# usomiq.net
KiCad netlist of a schematic drawn in Altium Designer
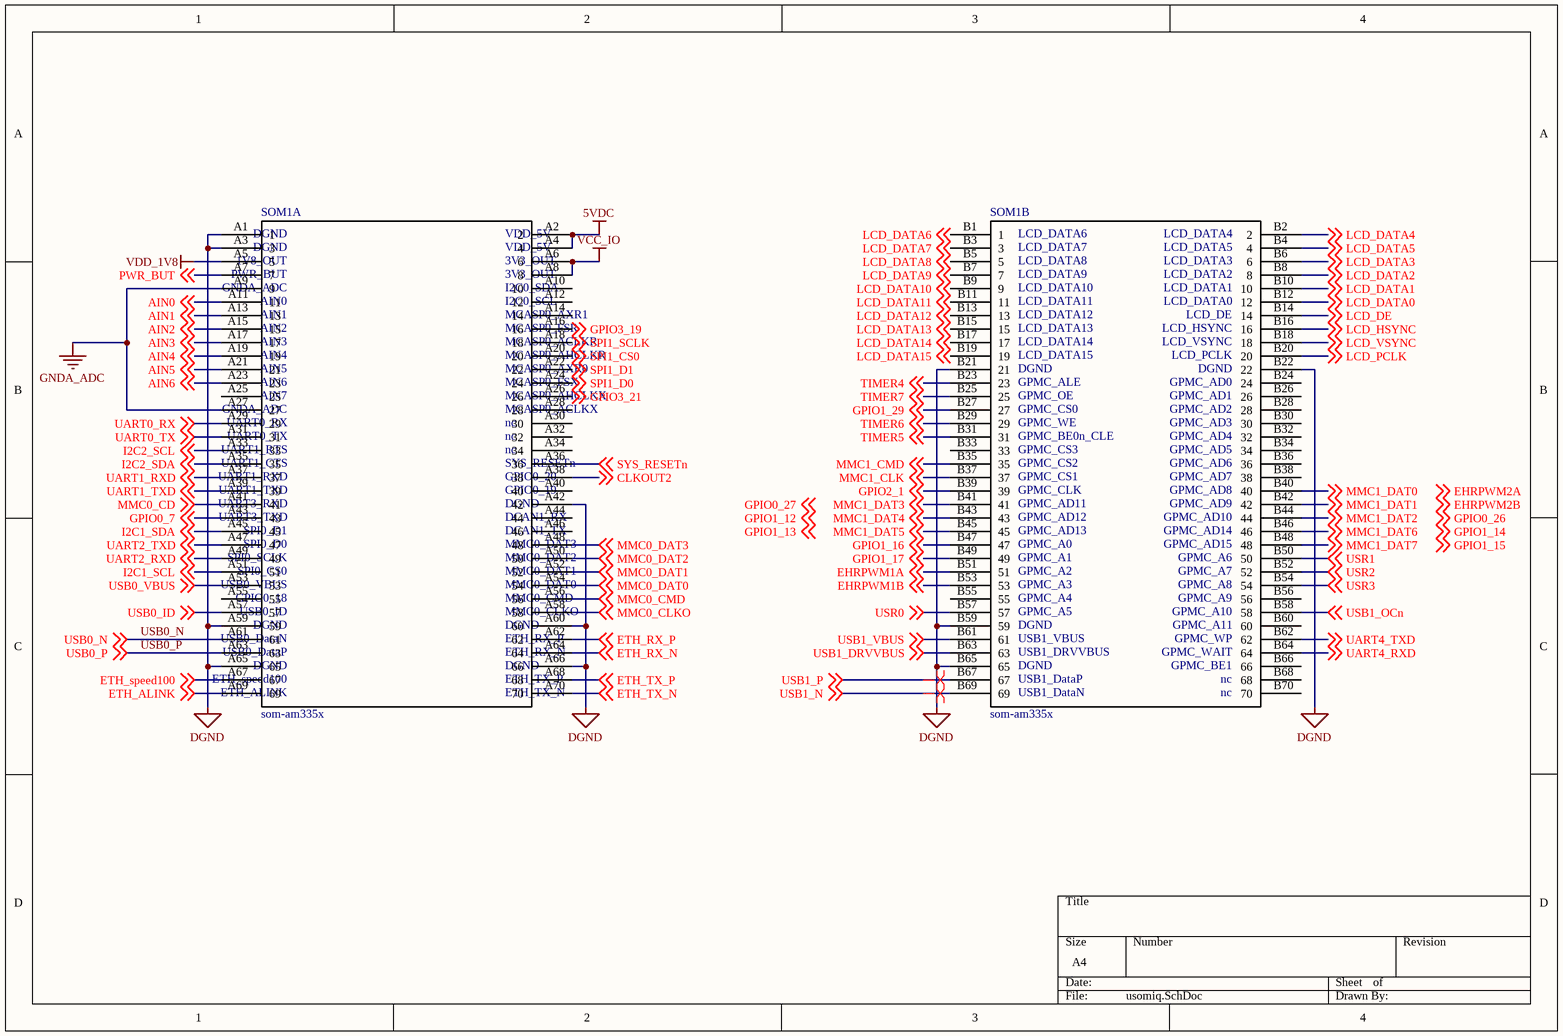
[diagram p0: usomiq.SchDoc]

(export (version "E")
  (design (tool "Eeschema 10.0.6"))
  (components
    (comp (ref "SOM1")
      (value "som-am335x")
      (footprint "am3359_module-sockets")
      (libsource (lib "usomiq-base") (part "som-am335x"))
    )
  )
  (nets
    (net (code "1") (name "5VDC") (class "Default")
      (node (ref "SOM1") (pin "A2") (pinfunction "2_A2") (pintype "passive"))
      (node (ref "SOM1") (pin "A4") (pinfunction "4_A4") (pintype "passive"))
    )
    (net (code "2") (name "AIN0") (class "Default")
      (node (ref "SOM1") (pin "A11") (pinfunction "11_A11") (pintype "passive"))
    )
    (net (code "3") (name "AIN1") (class "Default")
      (node (ref "SOM1") (pin "A13") (pinfunction "13_A13") (pintype "passive"))
    )
    (net (code "4") (name "AIN2") (class "Default")
      (node (ref "SOM1") (pin "A15") (pinfunction "15_A15") (pintype "passive"))
    )
    (net (code "5") (name "AIN3") (class "Default")
      (node (ref "SOM1") (pin "A17") (pinfunction "17_A17") (pintype "passive"))
    )
    (net (code "6") (name "AIN4") (class "Default")
      (node (ref "SOM1") (pin "A19") (pinfunction "19_A19") (pintype "passive"))
    )
    (net (code "7") (name "AIN5") (class "Default")
      (node (ref "SOM1") (pin "A21") (pinfunction "21_A21") (pintype "passive"))
    )
    (net (code "8") (name "AIN6") (class "Default")
      (node (ref "SOM1") (pin "A23") (pinfunction "23_A23") (pintype "passive"))
    )
    (net (code "9") (name "CLKOUT2") (class "Default")
      (node (ref "SOM1") (pin "A38") (pinfunction "38_A38") (pintype "passive"))
    )
    (net (code "10") (name "DGND") (class "Default")
      (node (ref "SOM1") (pin "A1") (pinfunction "1_A1") (pintype "passive"))
      (node (ref "SOM1") (pin "A3") (pinfunction "3_A3") (pintype "passive"))
      (node (ref "SOM1") (pin "A42") (pinfunction "42_A42") (pintype "passive"))
      (node (ref "SOM1") (pin "A59") (pinfunction "59_A59") (pintype "passive"))
      (node (ref "SOM1") (pin "A60") (pinfunction "60_A60") (pintype "passive"))
      (node (ref "SOM1") (pin "A65") (pinfunction "65_A65") (pintype "passive"))
      (node (ref "SOM1") (pin "A66") (pinfunction "66_A66") (pintype "passive"))
      (node (ref "SOM1") (pin "B21") (pinfunction "21_B21") (pintype "passive"))
      (node (ref "SOM1") (pin "B22") (pinfunction "22_B22") (pintype "passive"))
      (node (ref "SOM1") (pin "B59") (pinfunction "59_B59") (pintype "passive"))
      (node (ref "SOM1") (pin "B65") (pinfunction "65_B65") (pintype "passive"))
    )
    (net (code "11") (name "EHRPWM1A") (class "Default")
      (node (ref "SOM1") (pin "B51") (pinfunction "51_B51") (pintype "passive"))
    )
    (net (code "12") (name "EHRPWM1B") (class "Default")
      (node (ref "SOM1") (pin "B53") (pinfunction "53_B53") (pintype "passive"))
    )
    (net (code "15") (name "ETH_ALINK") (class "Default")
      (node (ref "SOM1") (pin "A69") (pinfunction "69_A69") (pintype "passive"))
    )
    (net (code "16") (name "ETH_RX_N") (class "Default")
      (node (ref "SOM1") (pin "A64") (pinfunction "64_A64") (pintype "passive"))
    )
    (net (code "17") (name "ETH_RX_P") (class "Default")
      (node (ref "SOM1") (pin "A62") (pinfunction "62_A62") (pintype "passive"))
    )
    (net (code "18") (name "ETH_TX_N") (class "Default")
      (node (ref "SOM1") (pin "A70") (pinfunction "70_A70") (pintype "passive"))
    )
    (net (code "19") (name "ETH_TX_P") (class "Default")
      (node (ref "SOM1") (pin "A68") (pinfunction "68_A68") (pintype "passive"))
    )
    (net (code "20") (name "ETH_speed100") (class "Default")
      (node (ref "SOM1") (pin "A67") (pinfunction "67_A67") (pintype "passive"))
    )
    (net (code "21") (name "GNDA_ADC") (class "Default")
      (node (ref "SOM1") (pin "A27") (pinfunction "27_A27") (pintype "passive"))
      (node (ref "SOM1") (pin "A9") (pinfunction "9_A9") (pintype "passive"))
    )
    (net (code "22") (name "GPIO0_7") (class "Default")
      (node (ref "SOM1") (pin "A43") (pinfunction "43_A43") (pintype "passive"))
    )
    (net (code "29") (name "GPIO1_16") (class "Default")
      (node (ref "SOM1") (pin "B47") (pinfunction "47_B47") (pintype "passive"))
    )
    (net (code "30") (name "GPIO1_17") (class "Default")
      (node (ref "SOM1") (pin "B49") (pinfunction "49_B49") (pintype "passive"))
    )
    (net (code "31") (name "GPIO1_29") (class "Default")
      (node (ref "SOM1") (pin "B27") (pinfunction "27_B27") (pintype "passive"))
    )
    (net (code "32") (name "GPIO2_1") (class "Default")
      (node (ref "SOM1") (pin "B39") (pinfunction "39_B39") (pintype "passive"))
    )
    (net (code "33") (name "GPIO3_19") (class "Default")
      (node (ref "SOM1") (pin "A16") (pinfunction "16_A16") (pintype "passive"))
    )
    (net (code "34") (name "GPIO3_21") (class "Default")
      (node (ref "SOM1") (pin "A26") (pinfunction "26_A26") (pintype "passive"))
    )
    (net (code "35") (name "I2C1_SCL") (class "Default")
      (node (ref "SOM1") (pin "A51") (pinfunction "51_A51") (pintype "passive"))
    )
    (net (code "36") (name "I2C1_SDA") (class "Default")
      (node (ref "SOM1") (pin "A45") (pinfunction "45_A45") (pintype "passive"))
    )
    (net (code "37") (name "I2C2_SCL") (class "Default")
      (node (ref "SOM1") (pin "A33") (pinfunction "33_A33") (pintype "passive"))
    )
    (net (code "38") (name "I2C2_SDA") (class "Default")
      (node (ref "SOM1") (pin "A35") (pinfunction "35_A35") (pintype "passive"))
    )
    (net (code "39") (name "LCD_DATA0") (class "Default")
      (node (ref "SOM1") (pin "B12") (pinfunction "12_B12") (pintype "passive"))
    )
    (net (code "40") (name "LCD_DATA1") (class "Default")
      (node (ref "SOM1") (pin "B10") (pinfunction "10_B10") (pintype "passive"))
    )
    (net (code "41") (name "LCD_DATA2") (class "Default")
      (node (ref "SOM1") (pin "B8") (pinfunction "8_B8") (pintype "passive"))
    )
    (net (code "42") (name "LCD_DATA3") (class "Default")
      (node (ref "SOM1") (pin "B6") (pinfunction "6_B6") (pintype "passive"))
    )
    (net (code "43") (name "LCD_DATA4") (class "Default")
      (node (ref "SOM1") (pin "B2") (pinfunction "2_B2") (pintype "passive"))
    )
    (net (code "44") (name "LCD_DATA5") (class "Default")
      (node (ref "SOM1") (pin "B4") (pinfunction "4_B4") (pintype "passive"))
    )
    (net (code "45") (name "LCD_DATA6") (class "Default")
      (node (ref "SOM1") (pin "B1") (pinfunction "1_B1") (pintype "passive"))
    )
    (net (code "46") (name "LCD_DATA7") (class "Default")
      (node (ref "SOM1") (pin "B3") (pinfunction "3_B3") (pintype "passive"))
    )
    (net (code "47") (name "LCD_DATA8") (class "Default")
      (node (ref "SOM1") (pin "B5") (pinfunction "5_B5") (pintype "passive"))
    )
    (net (code "48") (name "LCD_DATA9") (class "Default")
      (node (ref "SOM1") (pin "B7") (pinfunction "7_B7") (pintype "passive"))
    )
    (net (code "49") (name "LCD_DATA10") (class "Default")
      (node (ref "SOM1") (pin "B9") (pinfunction "9_B9") (pintype "passive"))
    )
    (net (code "50") (name "LCD_DATA11") (class "Default")
      (node (ref "SOM1") (pin "B11") (pinfunction "11_B11") (pintype "passive"))
    )
    (net (code "51") (name "LCD_DATA12") (class "Default")
      (node (ref "SOM1") (pin "B13") (pinfunction "13_B13") (pintype "passive"))
    )
    (net (code "52") (name "LCD_DATA13") (class "Default")
      (node (ref "SOM1") (pin "B15") (pinfunction "15_B15") (pintype "passive"))
    )
    (net (code "53") (name "LCD_DATA14") (class "Default")
      (node (ref "SOM1") (pin "B17") (pinfunction "17_B17") (pintype "passive"))
    )
    (net (code "54") (name "LCD_DATA15") (class "Default")
      (node (ref "SOM1") (pin "B19") (pinfunction "19_B19") (pintype "passive"))
    )
    (net (code "55") (name "LCD_DE") (class "Default")
      (node (ref "SOM1") (pin "B14") (pinfunction "14_B14") (pintype "passive"))
    )
    (net (code "56") (name "LCD_HSYNC") (class "Default")
      (node (ref "SOM1") (pin "B16") (pinfunction "16_B16") (pintype "passive"))
    )
    (net (code "57") (name "LCD_PCLK") (class "Default")
      (node (ref "SOM1") (pin "B20") (pinfunction "20_B20") (pintype "passive"))
    )
    (net (code "58") (name "LCD_VSYNC") (class "Default")
      (node (ref "SOM1") (pin "B18") (pinfunction "18_B18") (pintype "passive"))
    )
    (net (code "59") (name "MMC0_CD") (class "Default")
      (node (ref "SOM1") (pin "A41") (pinfunction "41_A41") (pintype "passive"))
    )
    (net (code "60") (name "MMC0_CLKO") (class "Default")
      (node (ref "SOM1") (pin "A58") (pinfunction "58_A58") (pintype "passive"))
    )
    (net (code "61") (name "MMC0_CMD") (class "Default")
      (node (ref "SOM1") (pin "A56") (pinfunction "56_A56") (pintype "passive"))
    )
    (net (code "62") (name "MMC0_DAT0") (class "Default")
      (node (ref "SOM1") (pin "A54") (pinfunction "54_A54") (pintype "passive"))
    )
    (net (code "63") (name "MMC0_DAT1") (class "Default")
      (node (ref "SOM1") (pin "A52") (pinfunction "52_A52") (pintype "passive"))
    )
    (net (code "64") (name "MMC0_DAT2") (class "Default")
      (node (ref "SOM1") (pin "A50") (pinfunction "50_A50") (pintype "passive"))
    )
    (net (code "65") (name "MMC0_DAT3") (class "Default")
      (node (ref "SOM1") (pin "A48") (pinfunction "48_A48") (pintype "passive"))
    )
    (net (code "66") (name "MMC1_CLK") (class "Default")
      (node (ref "SOM1") (pin "B37") (pinfunction "37_B37") (pintype "passive"))
    )
    (net (code "67") (name "MMC1_CMD") (class "Default")
      (node (ref "SOM1") (pin "B35") (pinfunction "35_B35") (pintype "passive"))
    )
    (net (code "68") (name "MMC1_DAT0") (class "Default")
      (node (ref "SOM1") (pin "B40") (pinfunction "40_B40") (pintype "passive"))
    )
    (net (code "69") (name "MMC1_DAT1") (class "Default")
      (node (ref "SOM1") (pin "B42") (pinfunction "42_B42") (pintype "passive"))
    )
    (net (code "70") (name "MMC1_DAT2") (class "Default")
      (node (ref "SOM1") (pin "B44") (pinfunction "44_B44") (pintype "passive"))
    )
    (net (code "71") (name "MMC1_DAT3") (class "Default")
      (node (ref "SOM1") (pin "B41") (pinfunction "41_B41") (pintype "passive"))
    )
    (net (code "72") (name "MMC1_DAT4") (class "Default")
      (node (ref "SOM1") (pin "B43") (pinfunction "43_B43") (pintype "passive"))
    )
    (net (code "73") (name "MMC1_DAT5") (class "Default")
      (node (ref "SOM1") (pin "B45") (pinfunction "45_B45") (pintype "passive"))
    )
    (net (code "74") (name "MMC1_DAT6") (class "Default")
      (node (ref "SOM1") (pin "B46") (pinfunction "46_B46") (pintype "passive"))
    )
    (net (code "75") (name "MMC1_DAT7") (class "Default")
      (node (ref "SOM1") (pin "B48") (pinfunction "48_B48") (pintype "passive"))
    )
    (net (code "76") (name "PWR_BUT") (class "Default")
      (node (ref "SOM1") (pin "A7") (pinfunction "7_A7") (pintype "passive"))
    )
    (net (code "77") (name "SPI1_CS0") (class "Default")
      (node (ref "SOM1") (pin "A20") (pinfunction "20_A20") (pintype "passive"))
    )
    (net (code "78") (name "SPI1_D0") (class "Default")
      (node (ref "SOM1") (pin "A24") (pinfunction "24_A24") (pintype "passive"))
    )
    (net (code "79") (name "SPI1_D1") (class "Default")
      (node (ref "SOM1") (pin "A22") (pinfunction "22_A22") (pintype "passive"))
    )
    (net (code "80") (name "SPI1_SCLK") (class "Default")
      (node (ref "SOM1") (pin "A18") (pinfunction "18_A18") (pintype "passive"))
    )
    (net (code "81") (name "SYS_RESETn") (class "Default")
      (node (ref "SOM1") (pin "A36") (pinfunction "36_A36") (pintype "passive"))
    )
    (net (code "82") (name "TIMER4") (class "Default")
      (node (ref "SOM1") (pin "B23") (pinfunction "23_B23") (pintype "passive"))
    )
    (net (code "83") (name "TIMER5") (class "Default")
      (node (ref "SOM1") (pin "B31") (pinfunction "31_B31") (pintype "passive"))
    )
    (net (code "84") (name "TIMER6") (class "Default")
      (node (ref "SOM1") (pin "B29") (pinfunction "29_B29") (pintype "passive"))
    )
    (net (code "85") (name "TIMER7") (class "Default")
      (node (ref "SOM1") (pin "B25") (pinfunction "25_B25") (pintype "passive"))
    )
    (net (code "86") (name "UART0_RX") (class "Default")
      (node (ref "SOM1") (pin "A29") (pinfunction "29_A29") (pintype "passive"))
    )
    (net (code "87") (name "UART0_TX") (class "Default")
      (node (ref "SOM1") (pin "A31") (pinfunction "31_A31") (pintype "passive"))
    )
    (net (code "88") (name "UART1_RXD") (class "Default")
      (node (ref "SOM1") (pin "A37") (pinfunction "37_A37") (pintype "passive"))
    )
    (net (code "89") (name "UART1_TXD") (class "Default")
      (node (ref "SOM1") (pin "A39") (pinfunction "39_A39") (pintype "passive"))
    )
    (net (code "90") (name "UART2_RXD") (class "Default")
      (node (ref "SOM1") (pin "A49") (pinfunction "49_A49") (pintype "passive"))
    )
    (net (code "91") (name "UART2_TXD") (class "Default")
      (node (ref "SOM1") (pin "A47") (pinfunction "47_A47") (pintype "passive"))
    )
    (net (code "92") (name "UART4_RXD") (class "Default")
      (node (ref "SOM1") (pin "B64") (pinfunction "64_B64") (pintype "passive"))
    )
    (net (code "93") (name "UART4_TXD") (class "Default")
      (node (ref "SOM1") (pin "B62") (pinfunction "62_B62") (pintype "passive"))
    )
    (net (code "94") (name "USB0_ID") (class "Default")
      (node (ref "SOM1") (pin "A57") (pinfunction "57_A57") (pintype "passive"))
    )
    (net (code "95") (name "USB0_N") (class "Default")
      (node (ref "SOM1") (pin "A61") (pinfunction "61_A61") (pintype "passive"))
    )
    (net (code "96") (name "USB0_P") (class "Default")
      (node (ref "SOM1") (pin "A63") (pinfunction "63_A63") (pintype "passive"))
    )
    (net (code "97") (name "USB0_VBUS") (class "Default")
      (node (ref "SOM1") (pin "A53") (pinfunction "53_A53") (pintype "passive"))
    )
    (net (code "98") (name "USB1_DRVVBUS") (class "Default")
      (node (ref "SOM1") (pin "B63") (pinfunction "63_B63") (pintype "passive"))
    )
    (net (code "99") (name "USB1_N") (class "Default")
      (node (ref "SOM1") (pin "B69") (pinfunction "69_B69") (pintype "passive"))
    )
    (net (code "100") (name "USB1_OCn") (class "Default")
      (node (ref "SOM1") (pin "B58") (pinfunction "58_B58") (pintype "passive"))
    )
    (net (code "101") (name "USB1_P") (class "Default")
      (node (ref "SOM1") (pin "B67") (pinfunction "67_B67") (pintype "passive"))
    )
    (net (code "102") (name "USB1_VBUS") (class "Default")
      (node (ref "SOM1") (pin "B61") (pinfunction "61_B61") (pintype "passive"))
    )
    (net (code "103") (name "USR0") (class "Default")
      (node (ref "SOM1") (pin "B57") (pinfunction "57_B57") (pintype "passive"))
    )
    (net (code "104") (name "USR1") (class "Default")
      (node (ref "SOM1") (pin "B50") (pinfunction "50_B50") (pintype "passive"))
    )
    (net (code "105") (name "USR2") (class "Default")
      (node (ref "SOM1") (pin "B52") (pinfunction "52_B52") (pintype "passive"))
    )
    (net (code "106") (name "USR3") (class "Default")
      (node (ref "SOM1") (pin "B54") (pinfunction "54_B54") (pintype "passive"))
    )
    (net (code "107") (name "VCC_IO") (class "Default")
      (node (ref "SOM1") (pin "A6") (pinfunction "6_A6") (pintype "passive"))
      (node (ref "SOM1") (pin "A8") (pinfunction "8_A8") (pintype "passive"))
    )
    (net (code "108") (name "VDD_1V8") (class "Default")
      (node (ref "SOM1") (pin "A5") (pinfunction "5_A5") (pintype "passive"))
    )
    (net (code "109") (name "unconnected-(SOM1A-10-PadA10)") (class "Default")
      (node (ref "SOM1") (pin "A10") (pinfunction "10_A10") (pintype "passive"))
    )
    (net (code "110") (name "unconnected-(SOM1A-12-PadA12)") (class "Default")
      (node (ref "SOM1") (pin "A12") (pinfunction "12_A12") (pintype "passive"))
    )
    (net (code "111") (name "unconnected-(SOM1A-14-PadA14)") (class "Default")
      (node (ref "SOM1") (pin "A14") (pinfunction "14_A14") (pintype "passive"))
    )
    (net (code "112") (name "unconnected-(SOM1A-25-PadA25)") (class "Default")
      (node (ref "SOM1") (pin "A25") (pinfunction "25_A25") (pintype "passive"))
    )
    (net (code "113") (name "unconnected-(SOM1A-28-PadA28)") (class "Default")
      (node (ref "SOM1") (pin "A28") (pinfunction "28_A28") (pintype "passive"))
    )
    (net (code "114") (name "unconnected-(SOM1A-30-PadA30)") (class "Default")
      (node (ref "SOM1") (pin "A30") (pinfunction "30_A30") (pintype "passive"))
    )
    (net (code "115") (name "unconnected-(SOM1A-32-PadA32)") (class "Default")
      (node (ref "SOM1") (pin "A32") (pinfunction "32_A32") (pintype "passive"))
    )
    (net (code "116") (name "unconnected-(SOM1A-34-PadA34)") (class "Default")
      (node (ref "SOM1") (pin "A34") (pinfunction "34_A34") (pintype "passive"))
    )
    (net (code "117") (name "unconnected-(SOM1A-40-PadA40)") (class "Default")
      (node (ref "SOM1") (pin "A40") (pinfunction "40_A40") (pintype "passive"))
    )
    (net (code "118") (name "unconnected-(SOM1A-44-PadA44)") (class "Default")
      (node (ref "SOM1") (pin "A44") (pinfunction "44_A44") (pintype "passive"))
    )
    (net (code "119") (name "unconnected-(SOM1A-46-PadA46)") (class "Default")
      (node (ref "SOM1") (pin "A46") (pinfunction "46_A46") (pintype "passive"))
    )
    (net (code "120") (name "unconnected-(SOM1A-55-PadA55)") (class "Default")
      (node (ref "SOM1") (pin "A55") (pinfunction "55_A55") (pintype "passive"))
    )
    (net (code "121") (name "unconnected-(SOM1B-24-PadB24)") (class "Default")
      (node (ref "SOM1") (pin "B24") (pinfunction "24_B24") (pintype "passive"))
    )
    (net (code "122") (name "unconnected-(SOM1B-26-PadB26)") (class "Default")
      (node (ref "SOM1") (pin "B26") (pinfunction "26_B26") (pintype "passive"))
    )
    (net (code "123") (name "unconnected-(SOM1B-28-PadB28)") (class "Default")
      (node (ref "SOM1") (pin "B28") (pinfunction "28_B28") (pintype "passive"))
    )
    (net (code "124") (name "unconnected-(SOM1B-30-PadB30)") (class "Default")
      (node (ref "SOM1") (pin "B30") (pinfunction "30_B30") (pintype "passive"))
    )
    (net (code "125") (name "unconnected-(SOM1B-32-PadB32)") (class "Default")
      (node (ref "SOM1") (pin "B32") (pinfunction "32_B32") (pintype "passive"))
    )
    (net (code "126") (name "unconnected-(SOM1B-33-PadB33)") (class "Default")
      (node (ref "SOM1") (pin "B33") (pinfunction "33_B33") (pintype "passive"))
    )
    (net (code "127") (name "unconnected-(SOM1B-34-PadB34)") (class "Default")
      (node (ref "SOM1") (pin "B34") (pinfunction "34_B34") (pintype "passive"))
    )
    (net (code "128") (name "unconnected-(SOM1B-36-PadB36)") (class "Default")
      (node (ref "SOM1") (pin "B36") (pinfunction "36_B36") (pintype "passive"))
    )
    (net (code "129") (name "unconnected-(SOM1B-38-PadB38)") (class "Default")
      (node (ref "SOM1") (pin "B38") (pinfunction "38_B38") (pintype "passive"))
    )
    (net (code "130") (name "unconnected-(SOM1B-55-PadB55)") (class "Default")
      (node (ref "SOM1") (pin "B55") (pinfunction "55_B55") (pintype "passive"))
    )
    (net (code "131") (name "unconnected-(SOM1B-56-PadB56)") (class "Default")
      (node (ref "SOM1") (pin "B56") (pinfunction "56_B56") (pintype "passive"))
    )
    (net (code "132") (name "unconnected-(SOM1B-60-PadB60)") (class "Default")
      (node (ref "SOM1") (pin "B60") (pinfunction "60_B60") (pintype "passive"))
    )
    (net (code "133") (name "unconnected-(SOM1B-66-PadB66)") (class "Default")
      (node (ref "SOM1") (pin "B66") (pinfunction "66_B66") (pintype "passive"))
    )
    (net (code "134") (name "unconnected-(SOM1B-68-PadB68)") (class "Default")
      (node (ref "SOM1") (pin "B68") (pinfunction "68_B68") (pintype "passive"))
    )
    (net (code "135") (name "unconnected-(SOM1B-70-PadB70)") (class "Default")
      (node (ref "SOM1") (pin "B70") (pinfunction "70_B70") (pintype "passive"))
    )
  )
)
